# Microcontroller_sch_v22_3.net
KiCad netlist of a schematic drawn in Altium Designer
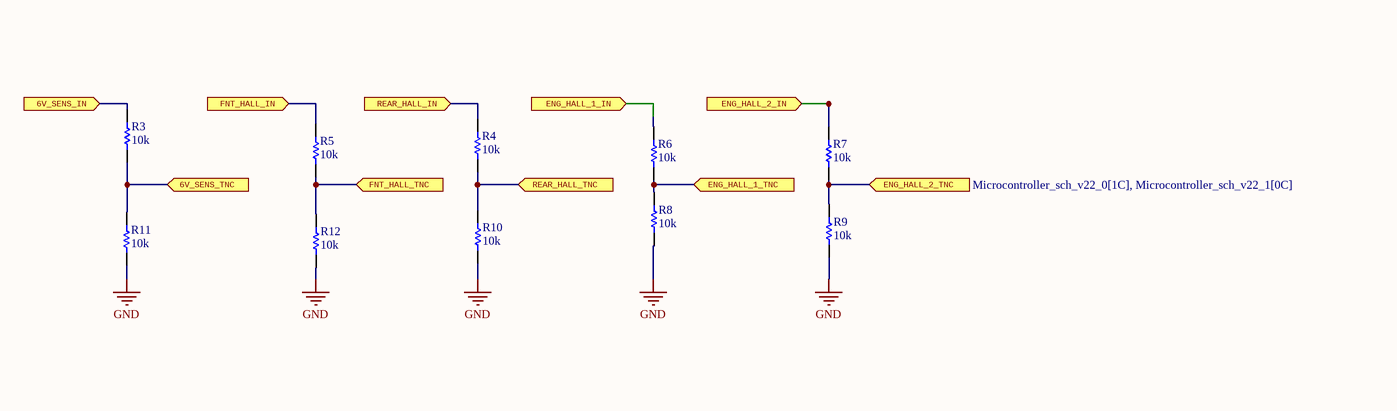
[diagram p0: Microcontroller_sch_v22_3.SchDoc]

(export (version "E")
  (design (tool "Eeschema 10.0.6"))
  (components
    (comp (ref "R3")
      (value "10k")
      (footprint "RESC2013X50X30LL20T20")
      (fields (field (name "MANUFACTURER") "Vishay Dale") (field (name "PART NUMBER") "CRCW08050000Z0EA"))
      (libsource (lib "Altium Content Vault") (part "RES"))
    )
    (comp (ref "R4")
      (value "10k")
      (footprint "RESC2013X50X30LL20T20")
      (fields (field (name "MANUFACTURER") "Vishay Dale") (field (name "PART NUMBER") "CRCW08050000Z0EA"))
      (libsource (lib "Altium Content Vault") (part "RES"))
    )
    (comp (ref "R5")
      (value "10k")
      (footprint "RESC2013X50X30LL20T20")
      (fields (field (name "MANUFACTURER") "Vishay Dale") (field (name "PART NUMBER") "CRCW08050000Z0EA"))
      (libsource (lib "Altium Content Vault") (part "RES"))
    )
    (comp (ref "R6")
      (value "10k")
      (footprint "RESC2013X50X30LL20T20")
      (fields (field (name "MANUFACTURER") "Vishay Dale") (field (name "PART NUMBER") "CRCW08050000Z0EA"))
      (libsource (lib "Altium Content Vault") (part "RES"))
    )
    (comp (ref "R7")
      (value "10k")
      (footprint "RESC2013X50X30LL20T20")
      (fields (field (name "MANUFACTURER") "Vishay Dale") (field (name "PART NUMBER") "CRCW08050000Z0EA"))
      (libsource (lib "Altium Content Vault") (part "RES"))
    )
    (comp (ref "R8")
      (value "10k")
      (footprint "RESC2013X50X30LL20T20")
      (fields (field (name "MANUFACTURER") "Vishay Dale") (field (name "PART NUMBER") "CRCW08050000Z0EA"))
      (libsource (lib "Altium Content Vault") (part "RES"))
    )
    (comp (ref "R9")
      (value "10k")
      (footprint "RESC2013X50X30LL20T20")
      (fields (field (name "MANUFACTURER") "Vishay Dale") (field (name "PART NUMBER") "CRCW08050000Z0EA"))
      (libsource (lib "Altium Content Vault") (part "RES"))
    )
    (comp (ref "R10")
      (value "10k")
      (footprint "RESC2013X50X30LL20T20")
      (fields (field (name "MANUFACTURER") "Vishay Dale") (field (name "PART NUMBER") "CRCW08050000Z0EA"))
      (libsource (lib "Altium Content Vault") (part "RES"))
    )
    (comp (ref "R11")
      (value "10k")
      (footprint "RESC2013X50X30LL20T20")
      (fields (field (name "MANUFACTURER") "Vishay Dale") (field (name "PART NUMBER") "CRCW08050000Z0EA"))
      (libsource (lib "Altium Content Vault") (part "RES"))
    )
    (comp (ref "R12")
      (value "10k")
      (footprint "RESC2013X50X30LL20T20")
      (fields (field (name "MANUFACTURER") "Vishay Dale") (field (name "PART NUMBER") "CRCW08050000Z0EA"))
      (libsource (lib "Altium Content Vault") (part "RES"))
    )
  )
  (nets
    (net (code "1") (name "/6V_SENS_IN") (class "Default")
      (node (ref "R3") (pin "2") (pinfunction "2_2") (pintype "passive"))
    )
    (net (code "2") (name "/6V_SENS_TNC") (class "Default")
      (node (ref "R11") (pin "2") (pinfunction "2_2") (pintype "passive"))
      (node (ref "R3") (pin "1") (pinfunction "1_1") (pintype "passive"))
    )
    (net (code "3") (name "/ENG_HALL_1_IN") (class "Default")
      (node (ref "R6") (pin "2") (pinfunction "2_2") (pintype "passive"))
    )
    (net (code "4") (name "/ENG_HALL_1_TNC") (class "Default")
      (node (ref "R6") (pin "1") (pinfunction "1_1") (pintype "passive"))
      (node (ref "R8") (pin "2") (pinfunction "2_2") (pintype "passive"))
    )
    (net (code "5") (name "/ENG_HALL_2_IN") (class "Default")
      (node (ref "R7") (pin "2") (pinfunction "2_2") (pintype "passive"))
    )
    (net (code "6") (name "/ENG_HALL_2_TNC") (class "Default")
      (node (ref "R7") (pin "1") (pinfunction "1_1") (pintype "passive"))
      (node (ref "R9") (pin "2") (pinfunction "2_2") (pintype "passive"))
    )
    (net (code "7") (name "/FNT_HALL_IN") (class "Default")
      (node (ref "R5") (pin "2") (pinfunction "2_2") (pintype "passive"))
    )
    (net (code "8") (name "/FNT_HALL_TNC") (class "Default")
      (node (ref "R12") (pin "2") (pinfunction "2_2") (pintype "passive"))
      (node (ref "R5") (pin "1") (pinfunction "1_1") (pintype "passive"))
    )
    (net (code "9") (name "/REAR_HALL_IN") (class "Default")
      (node (ref "R4") (pin "2") (pinfunction "2_2") (pintype "passive"))
    )
    (net (code "10") (name "/REAR_HALL_TNC") (class "Default")
      (node (ref "R10") (pin "2") (pinfunction "2_2") (pintype "passive"))
      (node (ref "R4") (pin "1") (pinfunction "1_1") (pintype "passive"))
    )
    (net (code "11") (name "GND") (class "Default")
      (node (ref "R10") (pin "1") (pinfunction "1_1") (pintype "passive"))
      (node (ref "R11") (pin "1") (pinfunction "1_1") (pintype "passive"))
      (node (ref "R12") (pin "1") (pinfunction "1_1") (pintype "passive"))
      (node (ref "R8") (pin "1") (pinfunction "1_1") (pintype "passive"))
      (node (ref "R9") (pin "1") (pinfunction "1_1") (pintype "passive"))
    )
  )
)
